# OMSI_TABLE_R12_v4.net
KiCad netlist of a schematic drawn in EAGLE
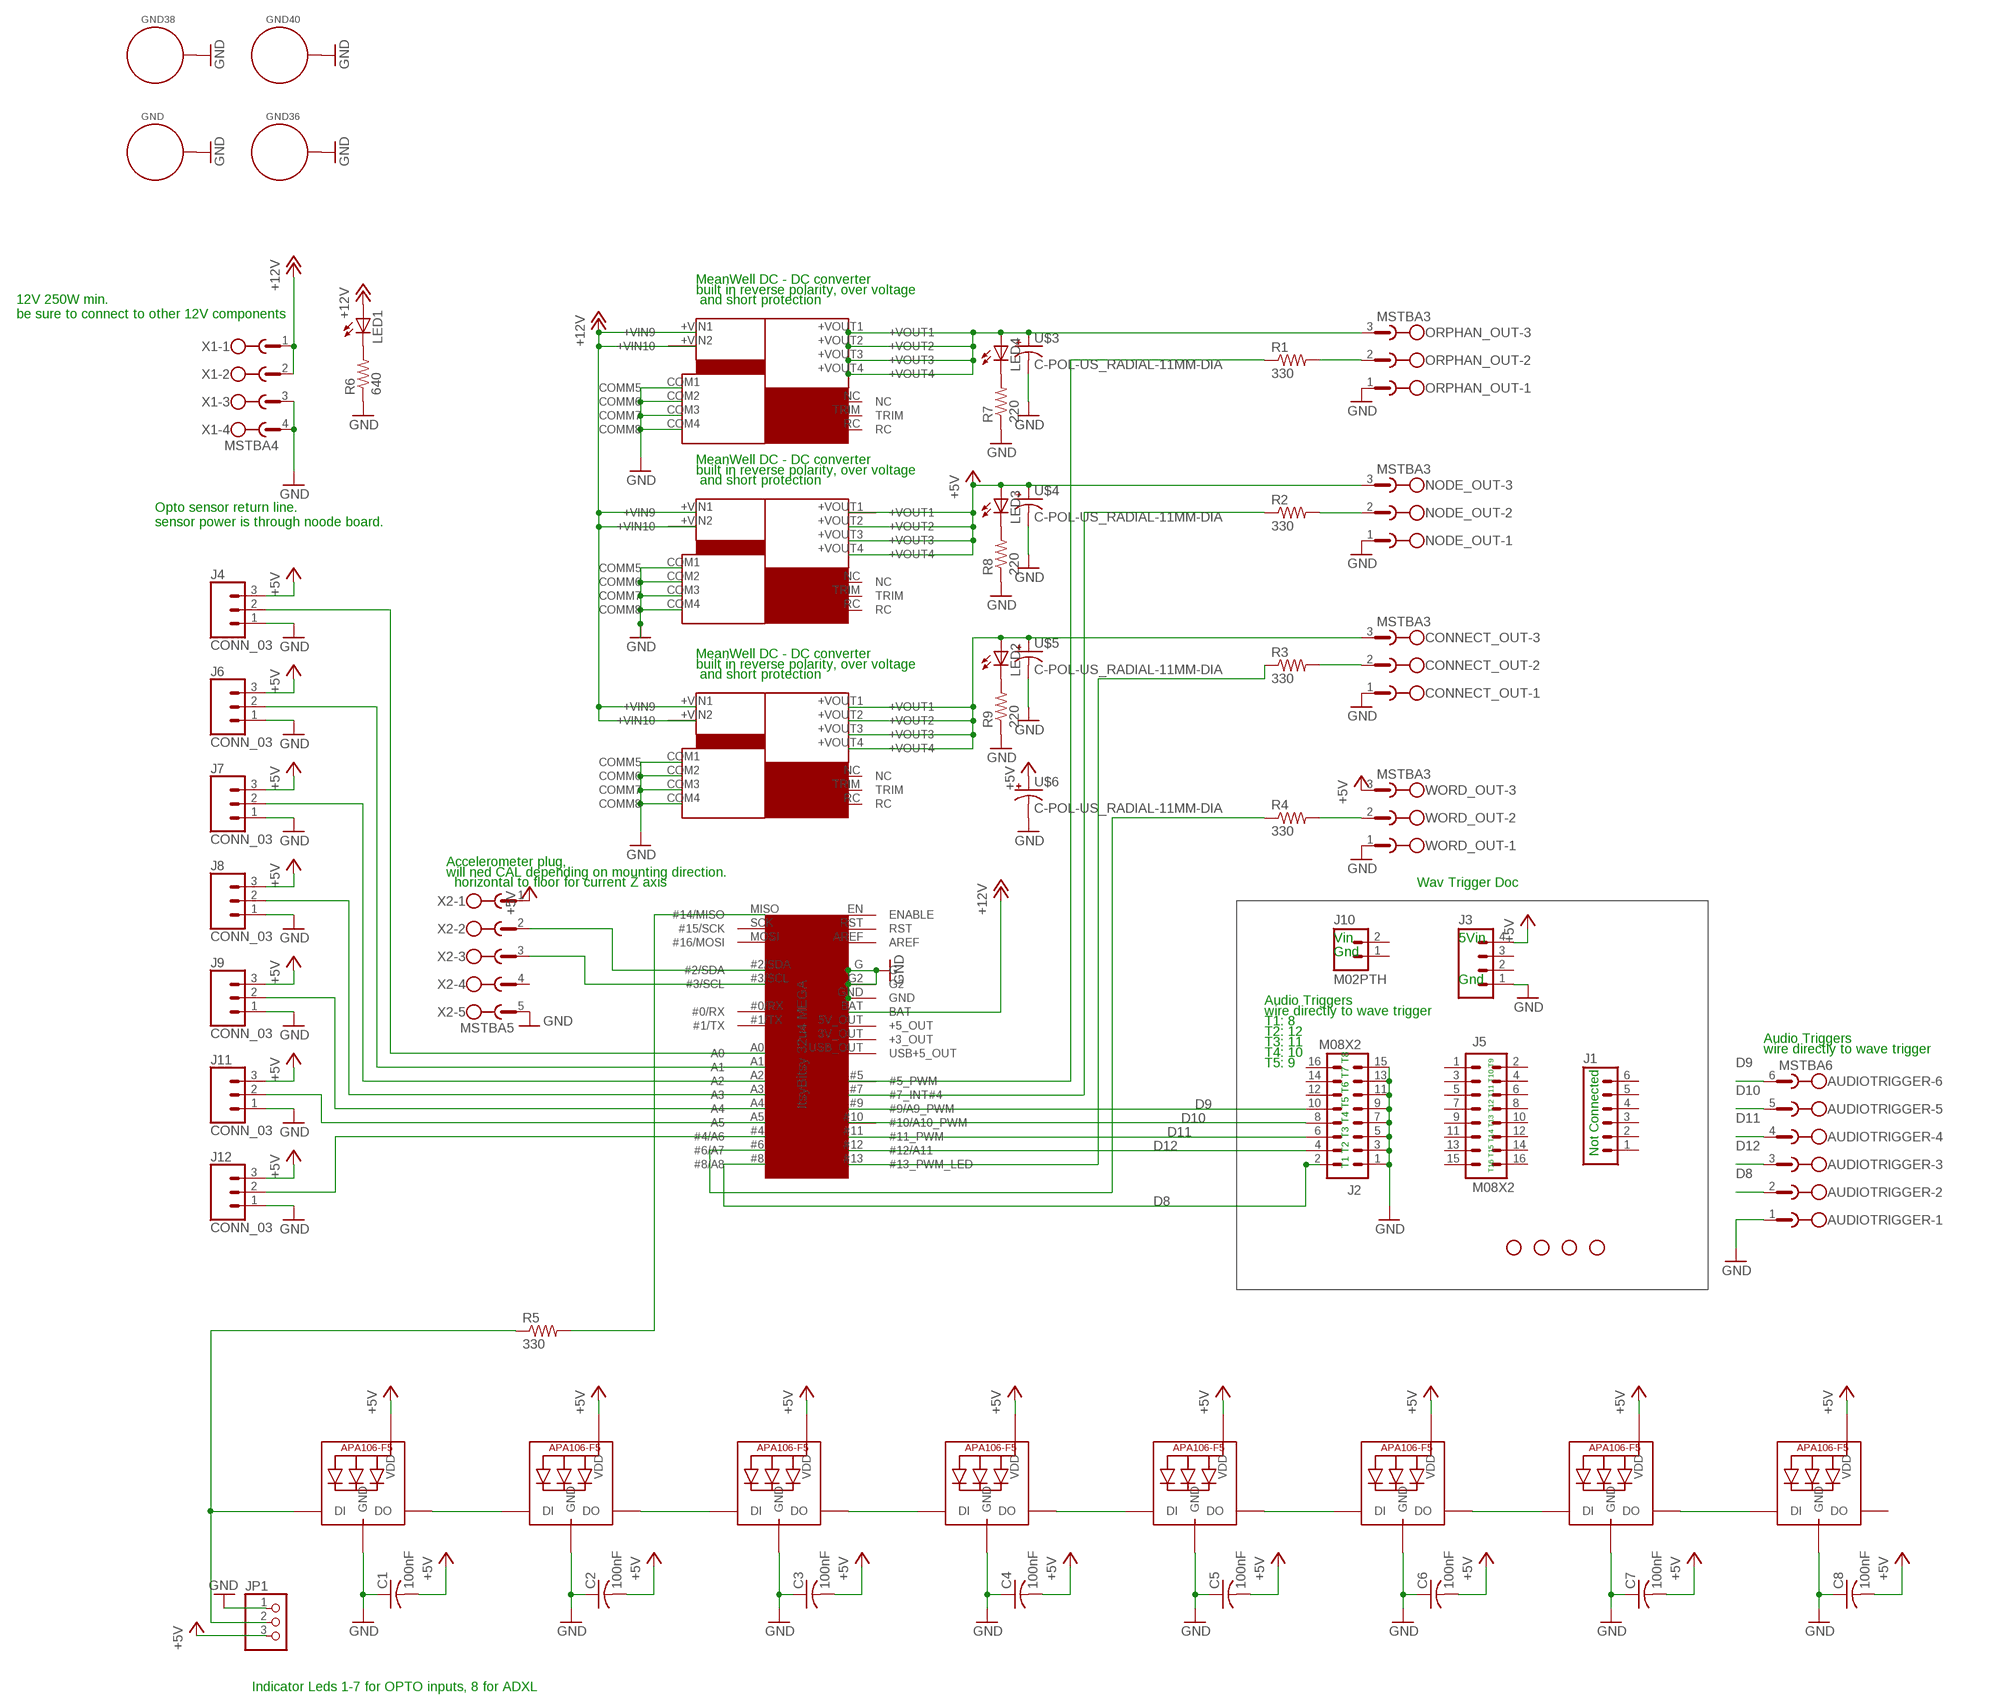
[diagram p0: schematic, sheet 1]

(export (version "E")
  (design (tool "Eeschema 10.0.6"))
  (components
    (comp (ref "AUDIOTRIGGER")
      (value "MSTBA6")
      (footprint "eagle-import:MSTBA6")
      (fields (field (name "MF") "FARNELL") (field (name "MPN") "1757284"))
      (libsource (lib "eagle-import") (part "MSTBA6"))
    )
    (comp (ref "C1")
      (value "100nF")
      (footprint "eagle-import:C0805")
      (libsource (lib "eagle-import") (part "C-USC0805"))
    )
    (comp (ref "C2")
      (value "100nF")
      (footprint "eagle-import:C0805")
      (libsource (lib "eagle-import") (part "C-USC0805"))
    )
    (comp (ref "C3")
      (value "100nF")
      (footprint "eagle-import:C0805")
      (libsource (lib "eagle-import") (part "C-USC0805"))
    )
    (comp (ref "C4")
      (value "100nF")
      (footprint "eagle-import:C0805")
      (libsource (lib "eagle-import") (part "C-USC0805"))
    )
    (comp (ref "C5")
      (value "100nF")
      (footprint "eagle-import:C0805")
      (libsource (lib "eagle-import") (part "C-USC0805"))
    )
    (comp (ref "C6")
      (value "100nF")
      (footprint "eagle-import:C0805")
      (libsource (lib "eagle-import") (part "C-USC0805"))
    )
    (comp (ref "C7")
      (value "100nF")
      (footprint "eagle-import:C0805")
      (libsource (lib "eagle-import") (part "C-USC0805"))
    )
    (comp (ref "C8")
      (value "100nF")
      (footprint "eagle-import:C0805")
      (libsource (lib "eagle-import") (part "C-USC0805"))
    )
    (comp (ref "CONNECT_OUT")
      (value "MSTBA3")
      (footprint "eagle-import:MSTBA3")
      (fields (field (name "MF") "FARNELL") (field (name "MPN") "1757255"))
      (libsource (lib "eagle-import") (part "MSTBA3"))
    )
    (comp (ref "GND")
      (value "STANDOFF_ELECTRICAL5-32")
      (footprint "eagle-import:STANDOFF_ELECTRICAL_5_32")
      (libsource (lib "eagle-import") (part "STANDOFF_ELECTRICAL5-32"))
    )
    (comp (ref "GND36")
      (value "STANDOFF_ELECTRICAL5-32")
      (footprint "eagle-import:STANDOFF_ELECTRICAL_5_32")
      (libsource (lib "eagle-import") (part "STANDOFF_ELECTRICAL5-32"))
    )
    (comp (ref "GND38")
      (value "STANDOFF_ELECTRICAL5-32")
      (footprint "eagle-import:STANDOFF_ELECTRICAL_5_32")
      (libsource (lib "eagle-import") (part "STANDOFF_ELECTRICAL5-32"))
    )
    (comp (ref "GND40")
      (value "STANDOFF_ELECTRICAL5-32")
      (footprint "eagle-import:STANDOFF_ELECTRICAL_5_32")
      (libsource (lib "eagle-import") (part "STANDOFF_ELECTRICAL5-32"))
    )
    (comp (ref "J1")
      (value "M06SIP")
      (footprint "eagle-import:1X06")
      (libsource (lib "eagle-import") (part "M06SIP"))
    )
    (comp (ref "J2")
      (value "M08X2")
      (footprint "eagle-import:2X8")
      (libsource (lib "eagle-import") (part "M08X2"))
    )
    (comp (ref "J3")
      (value "M04PTH")
      (footprint "eagle-import:1X04")
      (libsource (lib "eagle-import") (part "M04PTH"))
    )
    (comp (ref "J4")
      (value "CONN_03")
      (footprint "eagle-import:1X03_3.5MM_RA")
      (libsource (lib "eagle-import") (part "CONN_03"))
    )
    (comp (ref "J5")
      (value "M08X2")
      (footprint "eagle-import:2X8")
      (libsource (lib "eagle-import") (part "M08X2"))
    )
    (comp (ref "J6")
      (value "CONN_03")
      (footprint "eagle-import:1X03_3.5MM_RA")
      (libsource (lib "eagle-import") (part "CONN_03"))
    )
    (comp (ref "J7")
      (value "CONN_03")
      (footprint "eagle-import:1X03_3.5MM_RA")
      (libsource (lib "eagle-import") (part "CONN_03"))
    )
    (comp (ref "J8")
      (value "CONN_03")
      (footprint "eagle-import:1X03_3.5MM_RA")
      (libsource (lib "eagle-import") (part "CONN_03"))
    )
    (comp (ref "J9")
      (value "CONN_03")
      (footprint "eagle-import:1X03_3.5MM_RA")
      (libsource (lib "eagle-import") (part "CONN_03"))
    )
    (comp (ref "J10")
      (value "M02PTH")
      (footprint "eagle-import:1X02")
      (libsource (lib "eagle-import") (part "M02PTH"))
    )
    (comp (ref "J11")
      (value "CONN_03")
      (footprint "eagle-import:1X03_3.5MM_RA")
      (libsource (lib "eagle-import") (part "CONN_03"))
    )
    (comp (ref "J12")
      (value "CONN_03")
      (footprint "eagle-import:1X03_3.5MM_RA")
      (libsource (lib "eagle-import") (part "CONN_03"))
    )
    (comp (ref "JP1")
      (value "PINHD-1X3")
      (footprint "eagle-import:1X03")
      (libsource (lib "eagle-import") (part "PINHD-1X3"))
    )
    (comp (ref "LED1")
      (value "LEDCHIPLED_1206")
      (footprint "eagle-import:CHIPLED_1206")
      (libsource (lib "eagle-import") (part "LEDCHIPLED_1206"))
    )
    (comp (ref "LED2")
      (value "LEDCHIPLED_1206")
      (footprint "eagle-import:CHIPLED_1206")
      (libsource (lib "eagle-import") (part "LEDCHIPLED_1206"))
    )
    (comp (ref "LED3")
      (value "LEDCHIPLED_1206")
      (footprint "eagle-import:CHIPLED_1206")
      (libsource (lib "eagle-import") (part "LEDCHIPLED_1206"))
    )
    (comp (ref "LED4")
      (value "LEDCHIPLED_1206")
      (footprint "eagle-import:CHIPLED_1206")
      (libsource (lib "eagle-import") (part "LEDCHIPLED_1206"))
    )
    (comp (ref "LED5")
      (value "APA106-F5")
      (footprint "eagle-import:APA106-F5")
      (libsource (lib "eagle-import") (part "APA106-F5"))
    )
    (comp (ref "LED6")
      (value "APA106-F5")
      (footprint "eagle-import:APA106-F5")
      (libsource (lib "eagle-import") (part "APA106-F5"))
    )
    (comp (ref "LED7")
      (value "APA106-F5")
      (footprint "eagle-import:APA106-F5")
      (libsource (lib "eagle-import") (part "APA106-F5"))
    )
    (comp (ref "LED8")
      (value "APA106-F5")
      (footprint "eagle-import:APA106-F5")
      (libsource (lib "eagle-import") (part "APA106-F5"))
    )
    (comp (ref "LED9")
      (value "APA106-F5")
      (footprint "eagle-import:APA106-F5")
      (libsource (lib "eagle-import") (part "APA106-F5"))
    )
    (comp (ref "LED10")
      (value "APA106-F5")
      (footprint "eagle-import:APA106-F5")
      (libsource (lib "eagle-import") (part "APA106-F5"))
    )
    (comp (ref "LED11")
      (value "APA106-F5")
      (footprint "eagle-import:APA106-F5")
      (libsource (lib "eagle-import") (part "APA106-F5"))
    )
    (comp (ref "LED12")
      (value "APA106-F5")
      (footprint "eagle-import:APA106-F5")
      (libsource (lib "eagle-import") (part "APA106-F5"))
    )
    (comp (ref "MEANWELL_NID100_1")
      (value "MEANWELL_NID100")
      (footprint "eagle-import:MEANWELL_NID100")
      (libsource (lib "eagle-import") (part "MEANWELL_NID100"))
    )
    (comp (ref "MEANWELL_NID100_2")
      (value "MEANWELL_NID100")
      (footprint "eagle-import:MEANWELL_NID100")
      (libsource (lib "eagle-import") (part "MEANWELL_NID100"))
    )
    (comp (ref "MEANWELL_NID100_3")
      (value "MEANWELL_NID100")
      (footprint "eagle-import:MEANWELL_NID100")
      (libsource (lib "eagle-import") (part "MEANWELL_NID100"))
    )
    (comp (ref "NODE_OUT")
      (value "MSTBA3")
      (footprint "eagle-import:MSTBA3")
      (fields (field (name "MF") "FARNELL") (field (name "MPN") "1757255"))
      (libsource (lib "eagle-import") (part "MSTBA3"))
    )
    (comp (ref "ORPHAN_OUT")
      (value "MSTBA3")
      (footprint "eagle-import:MSTBA3")
      (fields (field (name "MF") "FARNELL") (field (name "MPN") "1757255"))
      (libsource (lib "eagle-import") (part "MSTBA3"))
    )
    (comp (ref "R1")
      (value "330")
      (footprint "eagle-import:RESAD1176W63L850D250B")
      (libsource (lib "eagle-import") (part "R-USAXIAL-11.7MM-PITCH_"))
    )
    (comp (ref "R2")
      (value "330")
      (footprint "eagle-import:RESAD1176W63L850D250B")
      (libsource (lib "eagle-import") (part "R-USAXIAL-11.7MM-PITCH_"))
    )
    (comp (ref "R3")
      (value "330")
      (footprint "eagle-import:RESAD1176W63L850D250B")
      (libsource (lib "eagle-import") (part "R-USAXIAL-11.7MM-PITCH_"))
    )
    (comp (ref "R4")
      (value "330")
      (footprint "eagle-import:RESAD1176W63L850D250B")
      (libsource (lib "eagle-import") (part "R-USAXIAL-11.7MM-PITCH_"))
    )
    (comp (ref "R5")
      (value "330")
      (footprint "eagle-import:RESAD1176W63L850D250B")
      (libsource (lib "eagle-import") (part "R-USAXIAL-11.7MM-PITCH_"))
    )
    (comp (ref "R6")
      (value "640")
      (footprint "eagle-import:R0805")
      (libsource (lib "eagle-import") (part "adafruit_420_R-US_R0805"))
    )
    (comp (ref "R7")
      (value "220")
      (footprint "eagle-import:R0805")
      (libsource (lib "eagle-import") (part "R-US_R0805"))
    )
    (comp (ref "R8")
      (value "220")
      (footprint "eagle-import:R0805")
      (libsource (lib "eagle-import") (part "R-US_R0805"))
    )
    (comp (ref "R9")
      (value "220")
      (footprint "eagle-import:R0805")
      (libsource (lib "eagle-import") (part "R-US_R0805"))
    )
    (comp (ref "STANDOFF5")
      (value "STAND-OFF")
      (footprint "eagle-import:STAND-OFF")
      (libsource (lib "eagle-import") (part "STAND-OFF"))
    )
    (comp (ref "STANDOFF6")
      (value "STAND-OFF")
      (footprint "eagle-import:STAND-OFF")
      (libsource (lib "eagle-import") (part "STAND-OFF"))
    )
    (comp (ref "STANDOFF7")
      (value "STAND-OFF")
      (footprint "eagle-import:STAND-OFF")
      (libsource (lib "eagle-import") (part "STAND-OFF"))
    )
    (comp (ref "STANDOFF8")
      (value "STAND-OFF")
      (footprint "eagle-import:STAND-OFF")
      (libsource (lib "eagle-import") (part "STAND-OFF"))
    )
    (comp (ref "U$1")
      (value "ITSYBITSY_32U4")
      (footprint "eagle-import:ITSYBITSY_32U4")
      (libsource (lib "eagle-import") (part "ITSYBITSY_32U4"))
    )
    (comp (ref "U$3")
      (value "C-POL-US_RADIAL-11MM-DIA")
      (footprint "eagle-import:CAPPRD508W65D1000H1100B")
      (libsource (lib "eagle-import") (part "C-POL-USRADIAL-11MM-DIA_"))
    )
    (comp (ref "U$4")
      (value "C-POL-US_RADIAL-11MM-DIA")
      (footprint "eagle-import:CAPPRD508W65D1000H1100B")
      (libsource (lib "eagle-import") (part "C-POL-USRADIAL-11MM-DIA_"))
    )
    (comp (ref "U$5")
      (value "C-POL-US_RADIAL-11MM-DIA")
      (footprint "eagle-import:CAPPRD508W65D1000H1100B")
      (libsource (lib "eagle-import") (part "C-POL-USRADIAL-11MM-DIA_"))
    )
    (comp (ref "U$6")
      (value "C-POL-US_RADIAL-11MM-DIA")
      (footprint "eagle-import:CAPPRD508W65D1000H1100B")
      (libsource (lib "eagle-import") (part "C-POL-USRADIAL-11MM-DIA_"))
    )
    (comp (ref "WORD_OUT")
      (value "MSTBA3")
      (footprint "eagle-import:MSTBA3")
      (fields (field (name "MF") "FARNELL") (field (name "MPN") "1757255"))
      (libsource (lib "eagle-import") (part "MSTBA3"))
    )
    (comp (ref "X1")
      (value "MSTBA4")
      (footprint "eagle-import:MSTBA4")
      (fields (field (name "MF") "FARNELL") (field (name "MPN") "1757268"))
      (libsource (lib "eagle-import") (part "MSTBA4"))
    )
    (comp (ref "X2")
      (value "MSTBA5")
      (footprint "eagle-import:MSTBA5")
      (fields (field (name "MPN") "1757271"))
      (libsource (lib "eagle-import") (part "MSTBA5"))
    )
  )
  (nets
    (net (code "1") (name "+5V") (class "Default")
      (node (ref "C1") (pin "2") (pinfunction "2_2") (pintype "passive"))
      (node (ref "C2") (pin "2") (pinfunction "2_2") (pintype "passive"))
      (node (ref "C3") (pin "2") (pinfunction "2_2") (pintype "passive"))
      (node (ref "C4") (pin "2") (pinfunction "2_2") (pintype "passive"))
      (node (ref "C5") (pin "2") (pinfunction "2_2") (pintype "passive"))
      (node (ref "C6") (pin "2") (pinfunction "2_2") (pintype "passive"))
      (node (ref "C7") (pin "2") (pinfunction "2_2") (pintype "passive"))
      (node (ref "C8") (pin "2") (pinfunction "2_2") (pintype "passive"))
      (node (ref "J11") (pin "3") (pinfunction "3_3") (pintype "passive"))
      (node (ref "J12") (pin "3") (pinfunction "3_3") (pintype "passive"))
      (node (ref "J3") (pin "4") (pinfunction "4_4") (pintype "passive"))
      (node (ref "J4") (pin "3") (pinfunction "3_3") (pintype "passive"))
      (node (ref "J6") (pin "3") (pinfunction "3_3") (pintype "passive"))
      (node (ref "J7") (pin "3") (pinfunction "3_3") (pintype "passive"))
      (node (ref "J8") (pin "3") (pinfunction "3_3") (pintype "passive"))
      (node (ref "J9") (pin "3") (pinfunction "3_3") (pintype "passive"))
      (node (ref "JP1") (pin "3") (pinfunction "3_3") (pintype "passive"))
      (node (ref "LED10") (pin "P$3") (pinfunction "VDD_P$3") (pintype "power_in"))
      (node (ref "LED11") (pin "P$3") (pinfunction "VDD_P$3") (pintype "power_in"))
      (node (ref "LED12") (pin "P$3") (pinfunction "VDD_P$3") (pintype "power_in"))
      (node (ref "LED3") (pin "A") (pinfunction "A_A") (pintype "passive"))
      (node (ref "LED5") (pin "P$3") (pinfunction "VDD_P$3") (pintype "power_in"))
      (node (ref "LED6") (pin "P$3") (pinfunction "VDD_P$3") (pintype "power_in"))
      (node (ref "LED7") (pin "P$3") (pinfunction "VDD_P$3") (pintype "power_in"))
      (node (ref "LED8") (pin "P$3") (pinfunction "VDD_P$3") (pintype "power_in"))
      (node (ref "LED9") (pin "P$3") (pinfunction "VDD_P$3") (pintype "power_in"))
      (node (ref "MEANWELL_NID100_3") (pin "+VOUT1") (pinfunction "+VOUT1_+VOUT1") (pintype "power_in"))
      (node (ref "MEANWELL_NID100_3") (pin "+VOUT2") (pinfunction "+VOUT2_+VOUT2") (pintype "power_in"))
      (node (ref "MEANWELL_NID100_3") (pin "+VOUT3") (pinfunction "+VOUT3_+VOUT3") (pintype "power_in"))
      (node (ref "MEANWELL_NID100_3") (pin "+VOUT4") (pinfunction "+VOUT4_+VOUT4") (pintype "power_in"))
      (node (ref "NODE_OUT") (pin "3") (pinfunction "1_3") (pintype "passive"))
      (node (ref "U$4") (pin "1") (pinfunction "+_1") (pintype "passive"))
      (node (ref "U$6") (pin "1") (pinfunction "+_1") (pintype "passive"))
      (node (ref "WORD_OUT") (pin "3") (pinfunction "1_3") (pintype "passive"))
      (node (ref "X2") (pin "1") (pinfunction "1_1") (pintype "passive"))
    )
    (net (code "2") (name "+12V") (class "Default")
      (node (ref "LED1") (pin "A") (pinfunction "A_A") (pintype "passive"))
      (node (ref "MEANWELL_NID100_1") (pin "+VIN1") (pinfunction "+VIN9_+VIN1") (pintype "power_in"))
      (node (ref "MEANWELL_NID100_1") (pin "+VIN2") (pinfunction "+VIN10_+VIN2") (pintype "power_in"))
      (node (ref "MEANWELL_NID100_2") (pin "+VIN1") (pinfunction "+VIN9_+VIN1") (pintype "power_in"))
      (node (ref "MEANWELL_NID100_2") (pin "+VIN2") (pinfunction "+VIN10_+VIN2") (pintype "power_in"))
      (node (ref "MEANWELL_NID100_3") (pin "+VIN1") (pinfunction "+VIN9_+VIN1") (pintype "power_in"))
      (node (ref "MEANWELL_NID100_3") (pin "+VIN2") (pinfunction "+VIN10_+VIN2") (pintype "power_in"))
      (node (ref "U$1") (pin "BAT") (pinfunction "BAT_BAT") (pintype "power_in"))
      (node (ref "X1") (pin "1") (pinfunction "1_1") (pintype "passive"))
      (node (ref "X1") (pin "2") (pinfunction "1_2") (pintype "passive"))
    )
    (net (code "3") (name "/+3_OUT") (class "Default")
      (node (ref "U$1") (pin "3V_OUT") (pinfunction "+3_OUT_3V_OUT") (pintype "power_in"))
    )
    (net (code "4") (name "/+5_OUT") (class "Default")
      (node (ref "U$1") (pin "5V_OUT") (pinfunction "+5_OUT_5V_OUT") (pintype "power_in"))
    )
    (net (code "5") (name "/AREF") (class "Default")
      (node (ref "U$1") (pin "AREF") (pinfunction "AREF_AREF") (pintype "power_in"))
    )
    (net (code "6") (name "/D8") (class "Default")
      (node (ref "AUDIOTRIGGER") (pin "2") (pinfunction "1_2") (pintype "passive"))
      (node (ref "J2") (pin "2") (pinfunction "2_2") (pintype "passive"))
      (node (ref "U$1") (pin "#8") (pinfunction "#8/A8_#8") (pintype "bidirectional"))
    )
    (net (code "7") (name "/D9") (class "Default")
      (node (ref "AUDIOTRIGGER") (pin "6") (pinfunction "1_6") (pintype "passive"))
      (node (ref "J2") (pin "10") (pinfunction "10_10") (pintype "passive"))
      (node (ref "U$1") (pin "#9") (pinfunction "#9/A9_PWM_#9") (pintype "bidirectional"))
    )
    (net (code "8") (name "/D10") (class "Default")
      (node (ref "AUDIOTRIGGER") (pin "5") (pinfunction "1_5") (pintype "passive"))
      (node (ref "J2") (pin "8") (pinfunction "8_8") (pintype "passive"))
      (node (ref "U$1") (pin "#10") (pinfunction "#10/A10_PWM_#10") (pintype "bidirectional"))
    )
    (net (code "9") (name "/D11") (class "Default")
      (node (ref "AUDIOTRIGGER") (pin "4") (pinfunction "1_4") (pintype "passive"))
      (node (ref "J2") (pin "6") (pinfunction "6_6") (pintype "passive"))
      (node (ref "U$1") (pin "#11") (pinfunction "#11_PWM_#11") (pintype "bidirectional"))
    )
    (net (code "10") (name "/D12") (class "Default")
      (node (ref "AUDIOTRIGGER") (pin "3") (pinfunction "1_3") (pintype "passive"))
      (node (ref "J2") (pin "4") (pinfunction "4_4") (pintype "passive"))
      (node (ref "U$1") (pin "#12") (pinfunction "#12/A11_#12") (pintype "bidirectional"))
    )
    (net (code "11") (name "/RST") (class "Default")
      (node (ref "U$1") (pin "RST") (pinfunction "RST_RST") (pintype "power_in"))
    )
    (net (code "12") (name "/USB+5_OUT") (class "Default")
      (node (ref "U$1") (pin "USB_OUT") (pinfunction "USB+5_OUT_USB_OUT") (pintype "power_in"))
    )
    (net (code "13") (name "GND") (class "Default")
      (node (ref "AUDIOTRIGGER") (pin "1") (pinfunction "1_1") (pintype "passive"))
      (node (ref "C1") (pin "1") (pinfunction "1_1") (pintype "passive"))
      (node (ref "C2") (pin "1") (pinfunction "1_1") (pintype "passive"))
      (node (ref "C3") (pin "1") (pinfunction "1_1") (pintype "passive"))
      (node (ref "C4") (pin "1") (pinfunction "1_1") (pintype "passive"))
      (node (ref "C5") (pin "1") (pinfunction "1_1") (pintype "passive"))
      (node (ref "C6") (pin "1") (pinfunction "1_1") (pintype "passive"))
      (node (ref "C7") (pin "1") (pinfunction "1_1") (pintype "passive"))
      (node (ref "C8") (pin "1") (pinfunction "1_1") (pintype "passive"))
      (node (ref "CONNECT_OUT") (pin "1") (pinfunction "1_1") (pintype "passive"))
      (node (ref "GND") (pin "P1") (pinfunction "P$1_P1") (pintype "bidirectional"))
      (node (ref "GND36") (pin "P1") (pinfunction "P$1_P1") (pintype "bidirectional"))
      (node (ref "GND38") (pin "P1") (pinfunction "P$1_P1") (pintype "bidirectional"))
      (node (ref "GND40") (pin "P1") (pinfunction "P$1_P1") (pintype "bidirectional"))
      (node (ref "J11") (pin "1") (pinfunction "1_1") (pintype "passive"))
      (node (ref "J12") (pin "1") (pinfunction "1_1") (pintype "passive"))
      (node (ref "J2") (pin "1") (pinfunction "1_1") (pintype "passive"))
      (node (ref "J2") (pin "11") (pinfunction "11_11") (pintype "passive"))
      (node (ref "J2") (pin "13") (pinfunction "13_13") (pintype "passive"))
      (node (ref "J2") (pin "15") (pinfunction "15_15") (pintype "passive"))
      (node (ref "J2") (pin "3") (pinfunction "3_3") (pintype "passive"))
      (node (ref "J2") (pin "5") (pinfunction "5_5") (pintype "passive"))
      (node (ref "J2") (pin "7") (pinfunction "7_7") (pintype "passive"))
      (node (ref "J2") (pin "9") (pinfunction "9_9") (pintype "passive"))
      (node (ref "J3") (pin "1") (pinfunction "1_1") (pintype "passive"))
      (node (ref "J4") (pin "1") (pinfunction "1_1") (pintype "passive"))
      (node (ref "J6") (pin "1") (pinfunction "1_1") (pintype "passive"))
      (node (ref "J7") (pin "1") (pinfunction "1_1") (pintype "passive"))
      (node (ref "J8") (pin "1") (pinfunction "1_1") (pintype "passive"))
      (node (ref "J9") (pin "1") (pinfunction "1_1") (pintype "passive"))
      (node (ref "JP1") (pin "1") (pinfunction "1_1") (pintype "passive"))
      (node (ref "LED10") (pin "P$2") (pinfunction "GND_P$2") (pintype "power_in"))
      (node (ref "LED11") (pin "P$2") (pinfunction "GND_P$2") (pintype "power_in"))
      (node (ref "LED12") (pin "P$2") (pinfunction "GND_P$2") (pintype "power_in"))
      (node (ref "LED5") (pin "P$2") (pinfunction "GND_P$2") (pintype "power_in"))
      (node (ref "LED6") (pin "P$2") (pinfunction "GND_P$2") (pintype "power_in"))
      (node (ref "LED7") (pin "P$2") (pinfunction "GND_P$2") (pintype "power_in"))
      (node (ref "LED8") (pin "P$2") (pinfunction "GND_P$2") (pintype "power_in"))
      (node (ref "LED9") (pin "P$2") (pinfunction "GND_P$2") (pintype "power_in"))
      (node (ref "MEANWELL_NID100_1") (pin "COM1") (pinfunction "COMM5_COM1") (pintype "power_in"))
      (node (ref "MEANWELL_NID100_1") (pin "COM2") (pinfunction "COMM6_COM2") (pintype "power_in"))
      (node (ref "MEANWELL_NID100_1") (pin "COM3") (pinfunction "COMM7_COM3") (pintype "power_in"))
      (node (ref "MEANWELL_NID100_1") (pin "COM4") (pinfunction "COMM8_COM4") (pintype "power_in"))
      (node (ref "MEANWELL_NID100_2") (pin "COM1") (pinfunction "COMM5_COM1") (pintype "power_in"))
      (node (ref "MEANWELL_NID100_2") (pin "COM2") (pinfunction "COMM6_COM2") (pintype "power_in"))
      (node (ref "MEANWELL_NID100_2") (pin "COM3") (pinfunction "COMM7_COM3") (pintype "power_in"))
      (node (ref "MEANWELL_NID100_2") (pin "COM4") (pinfunction "COMM8_COM4") (pintype "power_in"))
      (node (ref "MEANWELL_NID100_3") (pin "COM1") (pinfunction "COMM5_COM1") (pintype "power_in"))
      (node (ref "MEANWELL_NID100_3") (pin "COM2") (pinfunction "COMM6_COM2") (pintype "power_in"))
      (node (ref "MEANWELL_NID100_3") (pin "COM3") (pinfunction "COMM7_COM3") (pintype "power_in"))
      (node (ref "MEANWELL_NID100_3") (pin "COM4") (pinfunction "COMM8_COM4") (pintype "power_in"))
      (node (ref "NODE_OUT") (pin "1") (pinfunction "1_1") (pintype "passive"))
      (node (ref "ORPHAN_OUT") (pin "1") (pinfunction "1_1") (pintype "passive"))
      (node (ref "R6") (pin "1") (pinfunction "1_1") (pintype "passive"))
      (node (ref "R7") (pin "1") (pinfunction "1_1") (pintype "passive"))
      (node (ref "R8") (pin "1") (pinfunction "1_1") (pintype "passive"))
      (node (ref "R9") (pin "1") (pinfunction "1_1") (pintype "passive"))
      (node (ref "U$1") (pin "G") (pinfunction "G_G") (pintype "power_in"))
      (node (ref "U$1") (pin "G2") (pinfunction "G2_G2") (pintype "power_in"))
      (node (ref "U$1") (pin "GND") (pinfunction "GND_GND") (pintype "power_in"))
      (node (ref "U$3") (pin "2") (pinfunction "-_2") (pintype "passive"))
      (node (ref "U$4") (pin "2") (pinfunction "-_2") (pintype "passive"))
      (node (ref "U$5") (pin "2") (pinfunction "-_2") (pintype "passive"))
      (node (ref "U$6") (pin "2") (pinfunction "-_2") (pintype "passive"))
      (node (ref "WORD_OUT") (pin "1") (pinfunction "1_1") (pintype "passive"))
      (node (ref "X1") (pin "3") (pinfunction "1_3") (pintype "passive"))
      (node (ref "X1") (pin "4") (pinfunction "1_4") (pintype "passive"))
      (node (ref "X2") (pin "5") (pinfunction "1_5") (pintype "passive"))
    )
    (net (code "14") (name "Net-(CONNECT_OUTB-1)") (class "Default")
      (node (ref "CONNECT_OUT") (pin "2") (pinfunction "1_2") (pintype "passive"))
      (node (ref "R3") (pin "2") (pinfunction "2_2") (pintype "passive"))
    )
    (net (code "15") (name "Net-(CONNECT_OUTC-1)") (class "Default")
      (node (ref "CONNECT_OUT") (pin "3") (pinfunction "1_3") (pintype "passive"))
      (node (ref "LED2") (pin "A") (pinfunction "A_A") (pintype "passive"))
      (node (ref "MEANWELL_NID100_1") (pin "+VOUT1") (pinfunction "+VOUT1_+VOUT1") (pintype "power_in"))
      (node (ref "MEANWELL_NID100_1") (pin "+VOUT2") (pinfunction "+VOUT2_+VOUT2") (pintype "power_in"))
      (node (ref "MEANWELL_NID100_1") (pin "+VOUT3") (pinfunction "+VOUT3_+VOUT3") (pintype "power_in"))
      (node (ref "MEANWELL_NID100_1") (pin "+VOUT4") (pinfunction "+VOUT4_+VOUT4") (pintype "power_in"))
      (node (ref "U$5") (pin "1") (pinfunction "+_1") (pintype "passive"))
    )
    (net (code "16") (name "Net-(J4-Pad2)") (class "Default")
      (node (ref "J4") (pin "2") (pinfunction "2_2") (pintype "passive"))
      (node (ref "U$1") (pin "A0") (pinfunction "A0_A0") (pintype "bidirectional"))
    )
    (net (code "17") (name "Net-(J6-Pad2)") (class "Default")
      (node (ref "J6") (pin "2") (pinfunction "2_2") (pintype "passive"))
      (node (ref "U$1") (pin "A1") (pinfunction "A1_A1") (pintype "bidirectional"))
    )
    (net (code "18") (name "Net-(J7-Pad2)") (class "Default")
      (node (ref "J7") (pin "2") (pinfunction "2_2") (pintype "passive"))
      (node (ref "U$1") (pin "A2") (pinfunction "A2_A2") (pintype "bidirectional"))
    )
    (net (code "19") (name "Net-(J8-Pad2)") (class "Default")
      (node (ref "J8") (pin "2") (pinfunction "2_2") (pintype "passive"))
      (node (ref "U$1") (pin "A3") (pinfunction "A3_A3") (pintype "bidirectional"))
    )
    (net (code "20") (name "Net-(J9-Pad2)") (class "Default")
      (node (ref "J9") (pin "2") (pinfunction "2_2") (pintype "passive"))
      (node (ref "U$1") (pin "A4") (pinfunction "A4_A4") (pintype "bidirectional"))
    )
    (net (code "21") (name "Net-(J11-Pad2)") (class "Default")
      (node (ref "J11") (pin "2") (pinfunction "2_2") (pintype "passive"))
      (node (ref "U$1") (pin "A5") (pinfunction "A5_A5") (pintype "bidirectional"))
    )
    (net (code "22") (name "Net-(LED1-PadC)") (class "Default")
      (node (ref "LED1") (pin "C") (pinfunction "C_C") (pintype "passive"))
      (node (ref "R6") (pin "2") (pinfunction "2_2") (pintype "passive"))
    )
    (net (code "23") (name "Net-(LED2-PadC)") (class "Default")
      (node (ref "LED2") (pin "C") (pinfunction "C_C") (pintype "passive"))
      (node (ref "R9") (pin "2") (pinfunction "2_2") (pintype "passive"))
    )
    (net (code "24") (name "Net-(LED3-PadC)") (class "Default")
      (node (ref "LED3") (pin "C") (pinfunction "C_C") (pintype "passive"))
      (node (ref "R8") (pin "2") (pinfunction "2_2") (pintype "passive"))
    )
    (net (code "25") (name "Net-(LED4-PadC)") (class "Default")
      (node (ref "LED4") (pin "C") (pinfunction "C_C") (pintype "passive"))
      (node (ref "R7") (pin "2") (pinfunction "2_2") (pintype "passive"))
    )
    (net (code "26") (name "Net-(LED5-DI)") (class "Default")
      (node (ref "JP1") (pin "2") (pinfunction "2_2") (pintype "passive"))
      (node (ref "LED5") (pin "P$4") (pinfunction "DI_P$4") (pintype "input"))
      (node (ref "R5") (pin "1") (pinfunction "1_1") (pintype "passive"))
    )
    (net (code "27") (name "Net-(LED5-DO)") (class "Default")
      (node (ref "LED5") (pin "P$1") (pinfunction "DO_P$1") (pintype "output"))
      (node (ref "LED6") (pin "P$4") (pinfunction "DI_P$4") (pintype "input"))
    )
    (net (code "28") (name "Net-(LED6-DO)") (class "Default")
      (node (ref "LED6") (pin "P$1") (pinfunction "DO_P$1") (pintype "output"))
      (node (ref "LED7") (pin "P$4") (pinfunction "DI_P$4") (pintype "input"))
    )
    (net (code "29") (name "Net-(LED7-DO)") (class "Default")
      (node (ref "LED7") (pin "P$1") (pinfunction "DO_P$1") (pintype "output"))
      (node (ref "LED8") (pin "P$4") (pinfunction "DI_P$4") (pintype "input"))
    )
    (net (code "30") (name "Net-(LED8-DO)") (class "Default")
      (node (ref "LED8") (pin "P$1") (pinfunction "DO_P$1") (pintype "output"))
      (node (ref "LED9") (pin "P$4") (pinfunction "DI_P$4") (pintype "input"))
    )
    (net (code "31") (name "Net-(LED10-DI)") (class "Default")
      (node (ref "LED10") (pin "P$4") (pinfunction "DI_P$4") (pintype "input"))
      (node (ref "LED9") (pin "P$1") (pinfunction "DO_P$1") (pintype "output"))
    )
    (net (code "32") (name "Net-(LED10-DO)") (class "Default")
      (node (ref "LED10") (pin "P$1") (pinfunction "DO_P$1") (pintype "output"))
      (node (ref "LED11") (pin "P$4") (pinfunction "DI_P$4") (pintype "input"))
    )
    (net (code "33") (name "Net-(LED11-DO)") (class "Default")
      (node (ref "LED11") (pin "P$1") (pinfunction "DO_P$1") (pintype "output"))
      (node (ref "LED12") (pin "P$4") (pinfunction "DI_P$4") (pintype "input"))
    )
    (net (code "34") (name "Net-(NODE_OUTB-1)") (class "Default")
      (node (ref "NODE_OUT") (pin "2") (pinfunction "1_2") (pintype "passive"))
      (node (ref "R2") (pin "2") (pinfunction "2_2") (pintype "passive"))
    )
    (net (code "35") (name "Net-(ORPHAN_OUTB-1)") (class "Default")
      (node (ref "ORPHAN_OUT") (pin "2") (pinfunction "1_2") (pintype "passive"))
      (node (ref "R1") (pin "2") (pinfunction "2_2") (pintype "passive"))
    )
    (net (code "36") (name "Net-(ORPHAN_OUTC-1)") (class "Default")
      (node (ref "LED4") (pin "A") (pinfunction "A_A") (pintype "passive"))
      (node (ref "MEANWELL_NID100_2") (pin "+VOUT1") (pinfunction "+VOUT1_+VOUT1") (pintype "power_in"))
      (node (ref "MEANWELL_NID100_2") (pin "+VOUT2") (pinfunction "+VOUT2_+VOUT2") (pintype "power_in"))
      (node (ref "MEANWELL_NID100_2") (pin "+VOUT3") (pinfunction "+VOUT3_+VOUT3") (pintype "power_in"))
      (node (ref "MEANWELL_NID100_2") (pin "+VOUT4") (pinfunction "+VOUT4_+VOUT4") (pintype "power_in"))
      (node (ref "ORPHAN_OUT") (pin "3") (pinfunction "1_3") (pintype "passive"))
      (node (ref "U$3") (pin "1") (pinfunction "+_1") (pintype "passive"))
    )
    (net (code "37") (name "Net-(U$1-#4{slash}A6)") (class "Default")
      (node (ref "J12") (pin "2") (pinfunction "2_2") (pintype "passive"))
      (node (ref "U$1") (pin "#4") (pinfunction "#4/A6_#4") (pintype "input"))
    )
    (net (code "38") (name "Net-(U$1-#5_PWM)") (class "Default")
      (node (ref "R1") (pin "1") (pinfunction "1_1") (pintype "passive"))
      (node (ref "U$1") (pin "#5") (pinfunction "#5_PWM_#5") (pintype "bidirectional"))
    )
    (net (code "39") (name "Net-(U$1-#6{slash}A7)") (class "Default")
      (node (ref "R4") (pin "1") (pinfunction "1_1") (pintype "passive"))
      (node (ref "U$1") (pin "#6") (pinfunction "#6/A7_#6") (pintype "bidirectional"))
    )
    (net (code "40") (name "Net-(U$1-#7_INT#4)") (class "Default")
      (node (ref "R2") (pin "1") (pinfunction "1_1") (pintype "passive"))
      (node (ref "U$1") (pin "#7") (pinfunction "#7_INT#4_#7") (pintype "bidirectional"))
    )
    (net (code "41") (name "Net-(U$1-#13_PWM_LED)") (class "Default")
      (node (ref "R3") (pin "1") (pinfunction "1_1") (pintype "passive"))
      (node (ref "U$1") (pin "#13") (pinfunction "#13_PWM_LED_#13") (pintype "bidirectional"))
    )
    (net (code "42") (name "Net-(U$1-#14{slash}MISO)") (class "Default")
      (node (ref "R5") (pin "2") (pinfunction "2_2") (pintype "passive"))
      (node (ref "U$1") (pin "MISO") (pinfunction "#14/MISO_MISO") (pintype "bidirectional"))
    )
    (net (code "43") (name "Net-(WORD_OUTB-1)") (class "Default")
      (node (ref "R4") (pin "2") (pinfunction "2_2") (pintype "passive"))
      (node (ref "WORD_OUT") (pin "2") (pinfunction "1_2") (pintype "passive"))
    )
    (net (code "44") (name "Net-(X2B-1)") (class "Default")
      (node (ref "U$1") (pin "#2/SDA") (pinfunction "#2/SDA_#2/SDA") (pintype "bidirectional"))
      (node (ref "X2") (pin "2") (pinfunction "1_2") (pintype "passive"))
    )
    (net (code "45") (name "Net-(X2C-1)") (class "Default")
      (node (ref "U$1") (pin "#3/SCL") (pinfunction "#3/SCL_#3/SCL") (pintype "bidirectional"))
      (node (ref "X2") (pin "3") (pinfunction "1_3") (pintype "passive"))
    )
    (net (code "46") (name "unconnected-(J1-Pad1)") (class "Default")
      (node (ref "J1") (pin "1") (pinfunction "1_1") (pintype "passive"))
    )
    (net (code "47") (name "unconnected-(J1-Pad2)") (class "Default")
      (node (ref "J1") (pin "2") (pinfunction "2_2") (pintype "passive"))
    )
    (net (code "48") (name "unconnected-(J1-Pad3)") (class "Default")
      (node (ref "J1") (pin "3") (pinfunction "3_3") (pintype "passive"))
    )
    (net (code "49") (name "unconnected-(J1-Pad4)") (class "Default")
      (node (ref "J1") (pin "4") (pinfunction "4_4") (pintype "passive"))
    )
    (net (code "50") (name "unconnected-(J1-Pad5)") (class "Default")
      (node (ref "J1") (pin "5") (pinfunction "5_5") (pintype "passive"))
    )
    (net (code "51") (name "unconnected-(J1-Pad6)") (class "Default")
      (node (ref "J1") (pin "6") (pinfunction "6_6") (pintype "passive"))
    )
    (net (code "52") (name "unconnected-(J2-Pad12)") (class "Default")
      (node (ref "J2") (pin "12") (pinfunction "12_12") (pintype "passive"))
    )
    (net (code "53") (name "unconnected-(J2-Pad14)") (class "Default")
      (node (ref "J2") (pin "14") (pinfunction "14_14") (pintype "passive"))
    )
    (net (code "54") (name "unconnected-(J2-Pad16)") (class "Default")
      (node (ref "J2") (pin "16") (pinfunction "16_16") (pintype "passive"))
    )
    (net (code "55") (name "unconnected-(J3-Pad2)") (class "Default")
      (node (ref "J3") (pin "2") (pinfunction "2_2") (pintype "passive"))
    )
    (net (code "56") (name "unconnected-(J3-Pad3)") (class "Default")
      (node (ref "J3") (pin "3") (pinfunction "3_3") (pintype "passive"))
    )
    (net (code "57") (name "unconnected-(J5-Pad1)") (class "Default")
      (node (ref "J5") (pin "1") (pinfunction "1_1") (pintype "passive"))
    )
    (net (code "58") (name "unconnected-(J5-Pad2)") (class "Default")
      (node (ref "J5") (pin "2") (pinfunction "2_2") (pintype "passive"))
    )
    (net (code "59") (name "unconnected-(J5-Pad3)") (class "Default")
      (node (ref "J5") (pin "3") (pinfunction "3_3") (pintype "passive"))
    )
    (net (code "60") (name "unconnected-(J5-Pad4)") (class "Default")
      (node (ref "J5") (pin "4") (pinfunction "4_4") (pintype "passive"))
    )
    (net (code "61") (name "unconnected-(J5-Pad5)") (class "Default")
      (node (ref "J5") (pin "5") (pinfunction "5_5") (pintype "passive"))
    )
    (net (code "62") (name "unconnected-(J5-Pad6)") (class "Default")
      (node (ref "J5") (pin "6") (pinfunction "6_6") (pintype "passive"))
    )
    (net (code "63") (name "unconnected-(J5-Pad7)") (class "Default")
      (node (ref "J5") (pin "7") (pinfunction "7_7") (pintype "passive"))
    )
    (net (code "64") (name "unconnected-(J5-Pad8)") (class "Default")
      (node (ref "J5") (pin "8") (pinfunction "8_8") (pintype "passive"))
    )
    (net (code "65") (name "unconnected-(J5-Pad9)") (class "Default")
      (node (ref "J5") (pin "9") (pinfunction "9_9") (pintype "passive"))
    )
    (net (code "66") (name "unconnected-(J5-Pad10)") (class "Default")
      (node (ref "J5") (pin "10") (pinfunction "10_10") (pintype "passive"))
    )
    (net (code "67") (name "unconnected-(J5-Pad11)") (class "Default")
      (node (ref "J5") (pin "11") (pinfunction "11_11") (pintype "passive"))
    )
    (net (code "68") (name "unconnected-(J5-Pad12)") (class "Default")
      (node (ref "J5") (pin "12") (pinfunction "12_12") (pintype "passive"))
    )
    (net (code "69") (name "unconnected-(J5-Pad13)") (class "Default")
      (node (ref "J5") (pin "13") (pinfunction "13_13") (pintype "passive"))
    )
    (net (code "70") (name "unconnected-(J5-Pad14)") (class "Default")
      (node (ref "J5") (pin "14") (pinfunction "14_14") (pintype "passive"))
    )
    (net (code "71") (name "unconnected-(J5-Pad15)") (class "Default")
      (node (ref "J5") (pin "15") (pinfunction "15_15") (pintype "passive"))
    )
    (net (code "72") (name "unconnected-(J5-Pad16)") (class "Default")
      (node (ref "J5") (pin "16") (pinfunction "16_16") (pintype "passive"))
    )
    (net (code "73") (name "unconnected-(J10-Pad1)") (class "Default")
      (node (ref "J10") (pin "1") (pinfunction "1_1") (pintype "passive"))
    )
    (net (code "74") (name "unconnected-(J10-Pad2)") (class "Default")
      (node (ref "J10") (pin "2") (pinfunction "2_2") (pintype "passive"))
    )
    (net (code "75") (name "unconnected-(LED12-DO-PadP$1)") (class "Default")
      (node (ref "LED12") (pin "P$1") (pinfunction "DO_P$1") (pintype "output"))
    )
    (net (code "76") (name "unconnected-(MEANWELL_NID100_1-PadNC)") (class "Default")
      (node (ref "MEANWELL_NID100_1") (pin "NC") (pinfunction "NC_NC") (pintype "no_connect"))
    )
    (net (code "77") (name "unconnected-(MEANWELL_NID100_1-PadRC)") (class "Default")
      (node (ref "MEANWELL_NID100_1") (pin "RC") (pinfunction "RC_RC") (pintype "no_connect"))
    )
    (net (code "78") (name "unconnected-(MEANWELL_NID100_1-PadTRIM)") (class "Default")
      (node (ref "MEANWELL_NID100_1") (pin "TRIM") (pinfunction "TRIM_TRIM") (pintype "no_connect"))
    )
    (net (code "79") (name "unconnected-(MEANWELL_NID100_2-PadNC)") (class "Default")
      (node (ref "MEANWELL_NID100_2") (pin "NC") (pinfunction "NC_NC") (pintype "no_connect"))
    )
    (net (code "80") (name "unconnected-(MEANWELL_NID100_2-PadRC)") (class "Default")
      (node (ref "MEANWELL_NID100_2") (pin "RC") (pinfunction "RC_RC") (pintype "no_connect"))
    )
    (net (code "81") (name "unconnected-(MEANWELL_NID100_2-PadTRIM)") (class "Default")
      (node (ref "MEANWELL_NID100_2") (pin "TRIM") (pinfunction "TRIM_TRIM") (pintype "no_connect"))
    )
    (net (code "82") (name "unconnected-(MEANWELL_NID100_3-PadNC)") (class "Default")
      (node (ref "MEANWELL_NID100_3") (pin "NC") (pinfunction "NC_NC") (pintype "no_connect"))
    )
    (net (code "83") (name "unconnected-(MEANWELL_NID100_3-PadRC)") (class "Default")
      (node (ref "MEANWELL_NID100_3") (pin "RC") (pinfunction "RC_RC") (pintype "no_connect"))
    )
    (net (code "84") (name "unconnected-(MEANWELL_NID100_3-PadTRIM)") (class "Default")
      (node (ref "MEANWELL_NID100_3") (pin "TRIM") (pinfunction "TRIM_TRIM") (pintype "no_connect"))
    )
    (net (code "85") (name "unconnected-(U$1-#15{slash}SCK-PadSCK)") (class "Default")
      (node (ref "U$1") (pin "SCK") (pinfunction "#15/SCK_SCK") (pintype "bidirectional"))
    )
    (net (code "86") (name "unconnected-(U$1-#16{slash}MOSI-PadMOSI)") (class "Default")
      (node (ref "U$1") (pin "MOSI") (pinfunction "#16/MOSI_MOSI") (pintype "bidirectional"))
    )
    (net (code "87") (name "unconnected-(U$1-ENABLE-PadEN)") (class "Default")
      (node (ref "U$1") (pin "EN") (pinfunction "ENABLE_EN") (pintype "input"))
    )
    (net (code "88") (name "unconnected-(U$1-Pad#0{slash}RX)") (class "Default")
      (node (ref "U$1") (pin "#0/RX") (pinfunction "#0/RX_#0/RX") (pintype "bidirectional"))
    )
    (net (code "89") (name "unconnected-(U$1-Pad#1{slash}TX)") (class "Default")
      (node (ref "U$1") (pin "#1/TX") (pinfunction "#1/TX_#1/TX") (pintype "bidirectional"))
    )
    (net (code "90") (name "unconnected-(X2D-1-Pad4)") (class "Default")
      (node (ref "X2") (pin "4") (pinfunction "1_4") (pintype "passive"))
    )
  )
)
